# LightningDetector.net
KiCad netlist of a schematic drawn in Altium Designer
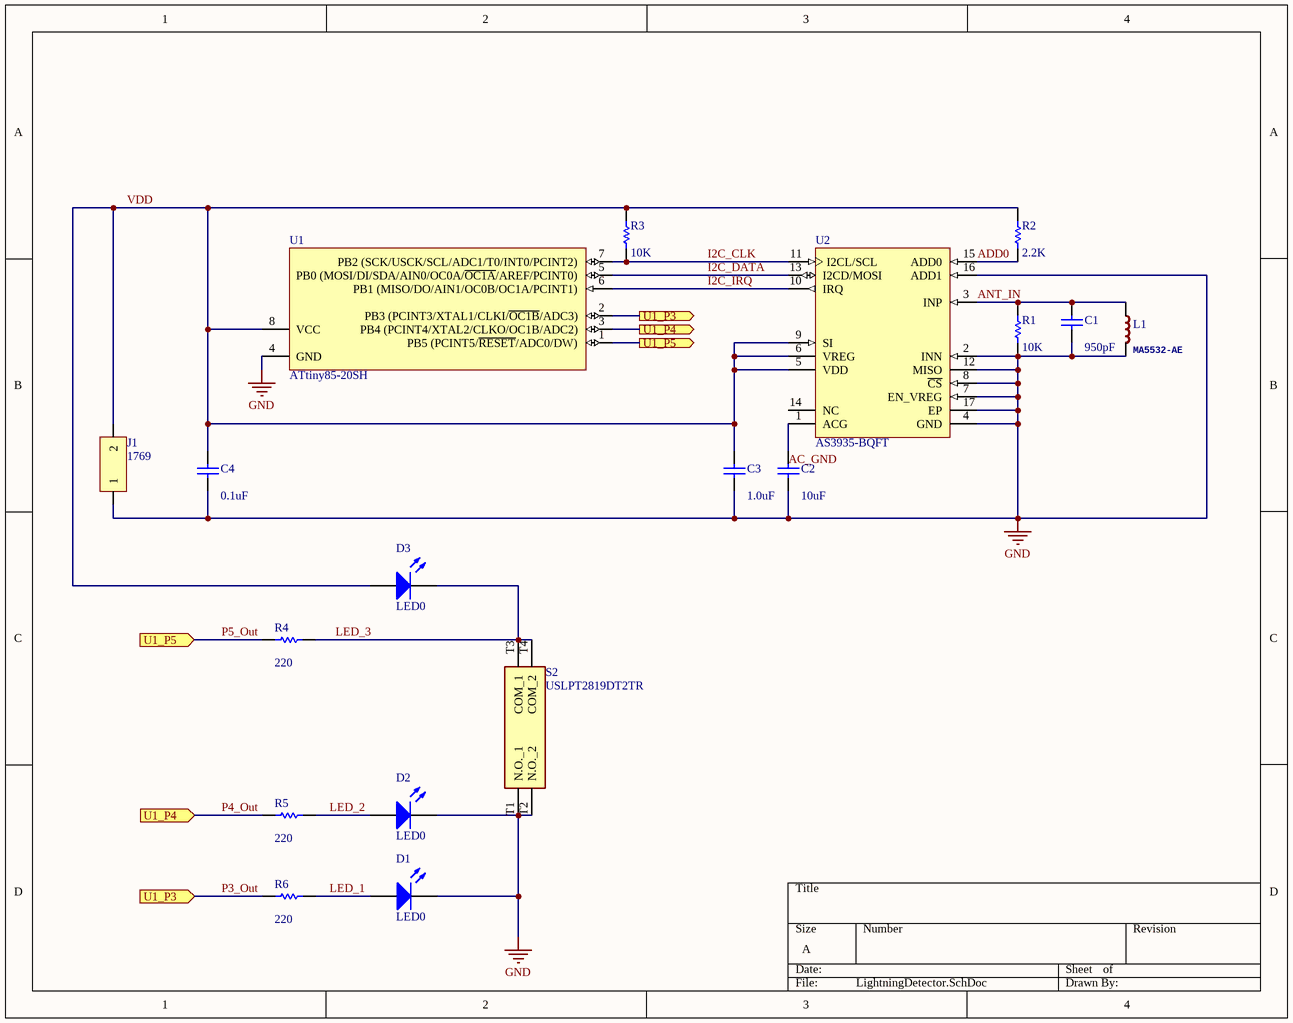
[diagram p0: LightningDetector.SchDoc]

(export (version "E")
  (design (tool "Eeschema 10.0.6"))
  (components
    (comp (ref "C1")
      (value "950pF")
      (footprint "0805")
      (description "SMD 0805 1nF    10% 50VDC")
      (fields (field (name "PART NUMBER") "885382207004"))
      (libsource (lib "Miscellaneous Devices") (part "Cap"))
    )
    (comp (ref "C2")
      (value "10uF")
      (footprint "0603")
      (description "SMD 0603 10uF  10% 6.3V")
      (fields (field (name "Comment") "JMK107ABJ106KA-T"))
      (libsource (lib "Miscellaneous Devices") (part "Cap"))
    )
    (comp (ref "C3")
      (value "1.0uF")
      (footprint "0603")
      (description "SMD 0603 1.0uF 10% 25V")
      (fields (field (name "Comment") "CC0603KRX5R8BB105"))
      (libsource (lib "Miscellaneous Devices") (part "Cap"))
    )
    (comp (ref "C4")
      (value "0.1uF")
      (footprint "0603")
      (description "Capacitor")
      (fields (field (name "Comment") "CC0603JRX7R9BB104"))
      (libsource (lib "Miscellaneous Devices") (part "Cap"))
    )
    (comp (ref "D1")
      (value "LED0")
      (footprint "0805")
      (description "Typical INFRARED GaAs LED")
      (fields (field (name "PUBLISHER") "Altium Limited"))
      (libsource (lib "Miscellaneous Devices") (part "LED0"))
    )
    (comp (ref "D2")
      (value "LED0")
      (footprint "0805")
      (description "Typical INFRARED GaAs LED")
      (fields (field (name "PUBLISHER") "Altium Limited"))
      (libsource (lib "Miscellaneous Devices") (part "LED0"))
    )
    (comp (ref "D3")
      (value "LED0")
      (footprint "0805")
      (description "Typical INFRARED GaAs LED")
      (fields (field (name "PUBLISHER") "Altium Limited"))
      (libsource (lib "Miscellaneous Devices") (part "LED0"))
    )
    (comp (ref "J1")
      (value "1769")
      (footprint "LD_PCBLib:1769")
      (description "Accessories JST 2 Pin power connector")
      (libsource (lib "LD_SchLib") (part "1769"))
    )
    (comp (ref "L1")
      (value "MA5532-AE")
      (footprint "MA5532-AE")
      (fields (field (name "LIBRARYNAME") "SparkFun-Coils"))
      (libsource (lib "SparkFun-Coils") (part "MA5532-AE"))
    )
    (comp (ref "R1")
      (value "10K")
      (footprint "0805")
      (description "Resistor")
      (fields (field (name "PART NUMBER") "WIN-T0805LF-11-1002-A"))
      (libsource (lib "Miscellaneous Devices") (part "Res1"))
    )
    (comp (ref "R2")
      (value "2.2K")
      (footprint "0603")
      (description "Resistor")
      (fields (field (name "PART NUMBER") "ESR03EZPJ222"))
      (libsource (lib "Miscellaneous Devices") (part "Res1"))
    )
    (comp (ref "R3")
      (value "10K")
      (footprint "0603")
      (description "Resistor")
      (fields (field (name "Comment") "CRCW060310K0JNEAC"))
      (libsource (lib "Miscellaneous Devices") (part "Res1"))
    )
    (comp (ref "R4")
      (value "220")
      (footprint "0603")
      (description "Resistor")
      (fields (field (name "Comment") "RC0603FR-07220RL"))
      (libsource (lib "Miscellaneous Devices") (part "Res1"))
    )
    (comp (ref "R5")
      (value "220")
      (footprint "0603")
      (description "Resistor")
      (fields (field (name "Comment") "RC0603FR-07220RL"))
      (libsource (lib "Miscellaneous Devices") (part "Res1"))
    )
    (comp (ref "R6")
      (value "220")
      (footprint "0603")
      (description "Resistor")
      (fields (field (name "Comment") "RC0603FR-07220RL"))
      (libsource (lib "Miscellaneous Devices") (part "Res1"))
    )
    (comp (ref "S2")
      (value "USLPT2819DT2TR")
      (footprint "SamacSys:USLPT2819DT2TR")
      (description "Tactile Switches")
      (fields (field (name "MOUSER PART NUMBER") "506-USLPT2819DT2TR"))
      (libsource (lib "*") (part "USLPT2819DT2TR"))
    )
    (comp (ref "U1")
      (value "ATtiny85-20SH")
      (footprint "8S2_L")
      (description "8-bit AVR Microcontroller, 20MHz, 2.7-5.5V")
      (libsource (lib "Altium Content Vault") (part "MC-8B-ATT25-IL8"))
    )
    (comp (ref "U2")
      (value "AS3935-BQFT")
      (footprint "AMS-MLPQ-16-4000X4000DE-2675X2675TP_N")
      (description "Franklin Lightning Sensor(TM) IC, 2.4 to 5.5 V, MLPQ-16, Pb-Free, Reel")
      (fields (field (name "MANUFACTURER") "AMS"))
      (libsource (lib "Altium Content Vault") (part "AMS-AS3935-MLPQ-16"))
    )
  )
  (nets
    (net (code "1") (name "/AC_GND") (class "Default")
      (node (ref "C2") (pin "2") (pinfunction "2_2") (pintype "passive"))
      (node (ref "U2") (pin "1") (pinfunction "ACG_1") (pintype "power_in"))
    )
    (net (code "2") (name "/ADD0") (class "Default")
      (node (ref "R2") (pin "1") (pinfunction "1_1") (pintype "passive"))
      (node (ref "U2") (pin "15") (pinfunction "ADD0_15") (pintype "input"))
    )
    (net (code "3") (name "/ANT_IN") (class "Default")
      (node (ref "C1") (pin "2") (pinfunction "2_2") (pintype "passive"))
      (node (ref "L1") (pin "1") (pinfunction "1_1") (pintype "passive"))
      (node (ref "R1") (pin "2") (pinfunction "2_2") (pintype "passive"))
      (node (ref "U2") (pin "3") (pinfunction "INP_3") (pintype "input"))
    )
    (net (code "4") (name "/I2C_CLK") (class "Default")
      (node (ref "R3") (pin "1") (pinfunction "1_1") (pintype "passive"))
      (node (ref "U1") (pin "7") (pinfunction "PB2_(SCK/USCK/SCL/ADC1/T0/INT0/PCINT2)_7") (pintype "bidirectional"))
      (node (ref "U2") (pin "11") (pinfunction "I2CL/SCL_11") (pintype "input"))
    )
    (net (code "5") (name "/I2C_DATA") (class "Default")
      (node (ref "U1") (pin "5") (pinfunction "PB0_(MOSI/DI/SDA/AIN0/OC0A/~{OC1A}/AREF/PCINT0)_5") (pintype "bidirectional"))
      (node (ref "U2") (pin "13") (pinfunction "I2CD/MOSI_13") (pintype "bidirectional"))
    )
    (net (code "6") (name "/I2C_IRQ") (class "Default")
      (node (ref "U1") (pin "6") (pinfunction "PB1_(MISO/DO/AIN1/OC0B/OC1A/PCINT1)_6") (pintype "input"))
      (node (ref "U2") (pin "10") (pinfunction "IRQ_10") (pintype "output"))
    )
    (net (code "7") (name "/LED_1") (class "Default")
      (node (ref "D1") (pin "1") (pinfunction "A_1") (pintype "passive"))
      (node (ref "R6") (pin "2") (pinfunction "2_2") (pintype "passive"))
    )
    (net (code "8") (name "/LED_2") (class "Default")
      (node (ref "D2") (pin "1") (pinfunction "A_1") (pintype "passive"))
      (node (ref "R5") (pin "2") (pinfunction "2_2") (pintype "passive"))
    )
    (net (code "9") (name "/LED_3") (class "Default")
      (node (ref "D3") (pin "2") (pinfunction "K_2") (pintype "passive"))
      (node (ref "R4") (pin "2") (pinfunction "2_2") (pintype "passive"))
      (node (ref "S2") (pin "T3") (pinfunction "COM_1_T3") (pintype "passive"))
      (node (ref "S2") (pin "T4") (pinfunction "COM_2_T4") (pintype "passive"))
    )
    (net (code "10") (name "/P3_Out") (class "Default")
      (node (ref "R6") (pin "1") (pinfunction "1_1") (pintype "passive"))
      (node (ref "U1") (pin "2") (pinfunction "PB3_(PCINT3/XTAL1/CLKI/~{OC1B}/ADC3)_2") (pintype "bidirectional"))
    )
    (net (code "11") (name "/P4_Out") (class "Default")
      (node (ref "R5") (pin "1") (pinfunction "1_1") (pintype "passive"))
      (node (ref "U1") (pin "3") (pinfunction "PB4_(PCINT4/XTAL2/CLKO/OC1B/ADC2)_3") (pintype "bidirectional"))
    )
    (net (code "12") (name "/P5_Out") (class "Default")
      (node (ref "R4") (pin "1") (pinfunction "1_1") (pintype "passive"))
      (node (ref "U1") (pin "1") (pinfunction "PB5_(PCINT5/~{RESET}/ADC0/DW)_1") (pintype "bidirectional"))
    )
    (net (code "13") (name "/VDD") (class "Default")
      (node (ref "C3") (pin "2") (pinfunction "2_2") (pintype "passive"))
      (node (ref "C4") (pin "2") (pinfunction "2_2") (pintype "passive"))
      (node (ref "D3") (pin "1") (pinfunction "A_1") (pintype "passive"))
      (node (ref "J1") (pin "2") (pinfunction "2_2") (pintype "passive"))
      (node (ref "R2") (pin "2") (pinfunction "2_2") (pintype "passive"))
      (node (ref "R3") (pin "2") (pinfunction "2_2") (pintype "passive"))
      (node (ref "U1") (pin "8") (pinfunction "VCC_8") (pintype "power_in"))
      (node (ref "U2") (pin "5") (pinfunction "VDD_5") (pintype "power_in"))
      (node (ref "U2") (pin "6") (pinfunction "VREG_6") (pintype "power_in"))
      (node (ref "U2") (pin "9") (pinfunction "SI_9") (pintype "input"))
    )
    (net (code "14") (name "GND") (class "Default")
      (node (ref "C1") (pin "1") (pinfunction "1_1") (pintype "passive"))
      (node (ref "C2") (pin "1") (pinfunction "1_1") (pintype "passive"))
      (node (ref "C3") (pin "1") (pinfunction "1_1") (pintype "passive"))
      (node (ref "C4") (pin "1") (pinfunction "1_1") (pintype "passive"))
      (node (ref "D1") (pin "2") (pinfunction "K_2") (pintype "passive"))
      (node (ref "D2") (pin "2") (pinfunction "K_2") (pintype "passive"))
      (node (ref "J1") (pin "1") (pinfunction "1_1") (pintype "passive"))
      (node (ref "L1") (pin "2") (pinfunction "2_2") (pintype "passive"))
      (node (ref "R1") (pin "1") (pinfunction "1_1") (pintype "passive"))
      (node (ref "S2") (pin "T1") (pinfunction "N.O._1_T1") (pintype "passive"))
      (node (ref "S2") (pin "T2") (pinfunction "N.O._2_T2") (pintype "passive"))
      (node (ref "U1") (pin "4") (pinfunction "GND_4") (pintype "power_in"))
      (node (ref "U2") (pin "12") (pinfunction "MISO_12") (pintype "power_in"))
      (node (ref "U2") (pin "16") (pinfunction "ADD1_16") (pintype "input"))
      (node (ref "U2") (pin "17") (pinfunction "EP_17") (pintype "power_in"))
      (node (ref "U2") (pin "2") (pinfunction "INN_2") (pintype "input"))
      (node (ref "U2") (pin "4") (pinfunction "GND_4") (pintype "power_in"))
      (node (ref "U2") (pin "7") (pinfunction "EN_VREG_7") (pintype "input"))
      (node (ref "U2") (pin "8") (pinfunction "~{CS}_8") (pintype "input"))
    )
    (net (code "15") (name "unconnected-(U2-NC-Pad14)") (class "Default")
      (node (ref "U2") (pin "14") (pinfunction "NC_14") (pintype "passive"))
    )
  )
)
